# SCH_2-way_Traffic.net
KiCad netlist of a schematic drawn in Altium Designer
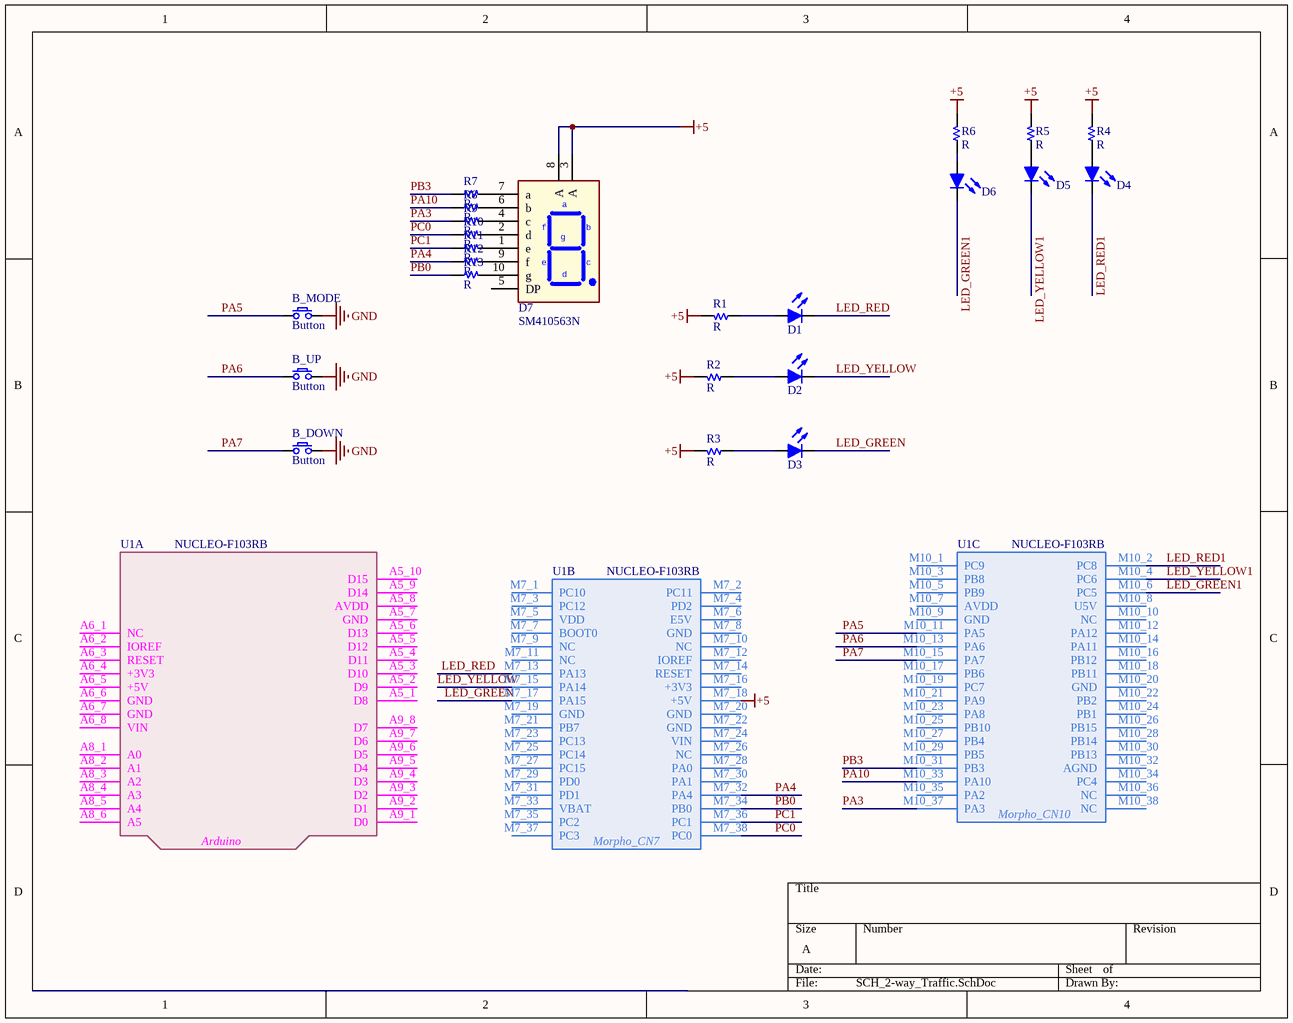
[diagram p0: SCH_2-way_Traffic.SchDoc]

(export (version "E")
  (design (tool "Eeschema 10.0.6"))
  (components
    (comp (ref "B_DOWN")
      (value "Button")
      (footprint "SW/2/DIP")
      (description "Tact switch 2 pin")
      (libsource (lib "chipfc_altium_libs") (part "SW SPST"))
    )
    (comp (ref "B_MODE")
      (value "Button")
      (footprint "SW/2/DIP")
      (description "Tact switch 2 pin")
      (libsource (lib "chipfc_altium_libs") (part "SW SPST"))
    )
    (comp (ref "B_UP")
      (value "Button")
      (footprint "SW/2/DIP")
      (description "Tact switch 2 pin")
      (libsource (lib "chipfc_altium_libs") (part "SW SPST"))
    )
    (comp (ref "D1")
      (value "Led")
      (footprint "LED 5MM - RED")
      (description "Typical LED")
      (libsource (lib "chipfc_altium_libs") (part "Led"))
    )
    (comp (ref "D2")
      (value "Led")
      (footprint "LED 5MM - WHITE")
      (description "Typical LED")
      (libsource (lib "chipfc_altium_libs") (part "Led"))
    )
    (comp (ref "D3")
      (value "Led")
      (footprint "LED 5MM - GREEN")
      (description "Typical LED")
      (libsource (lib "chipfc_altium_libs") (part "Led"))
    )
    (comp (ref "D4")
      (value "Led")
      (footprint "LED 5MM - RED")
      (description "Typical LED")
      (libsource (lib "chipfc_altium_libs") (part "Led"))
    )
    (comp (ref "D5")
      (value "Led")
      (footprint "LED 5MM - WHITE")
      (description "Typical LED")
      (libsource (lib "chipfc_altium_libs") (part "Led"))
    )
    (comp (ref "D6")
      (value "Led")
      (footprint "LED 5MM - GREEN")
      (description "Typical LED")
      (libsource (lib "chipfc_altium_libs") (part "Led"))
    )
    (comp (ref "D7")
      (value "SM410563N")
      (footprint "LED/7SEG/0.56")
      (description "SM410563N, Common-Anode, LED 7-seg, RED, 0.56\",")
      (libsource (lib "bk2022") (part "LED 7-SEG SM410563N"))
    )
    (comp (ref "R1")
      (value "R")
      (footprint "R 0805")
      (description "Resistor")
      (libsource (lib "chipfc_altium_libs") (part "Resistor"))
    )
    (comp (ref "R2")
      (value "R")
      (footprint "R 0805")
      (description "Resistor")
      (libsource (lib "chipfc_altium_libs") (part "Resistor"))
    )
    (comp (ref "R3")
      (value "R")
      (footprint "R 0805")
      (description "Resistor")
      (libsource (lib "chipfc_altium_libs") (part "Resistor"))
    )
    (comp (ref "R4")
      (value "R")
      (footprint "R 0805")
      (description "Resistor")
      (libsource (lib "chipfc_altium_libs") (part "Resistor"))
    )
    (comp (ref "R5")
      (value "R")
      (footprint "R 0805")
      (description "Resistor")
      (libsource (lib "chipfc_altium_libs") (part "Resistor"))
    )
    (comp (ref "R6")
      (value "R")
      (footprint "R 0805")
      (description "Resistor")
      (libsource (lib "chipfc_altium_libs") (part "Resistor"))
    )
    (comp (ref "R7")
      (value "R")
      (footprint "R 0805")
      (description "Resistor")
      (libsource (lib "chipfc_altium_libs") (part "Resistor"))
    )
    (comp (ref "R8")
      (value "R")
      (footprint "R 0805")
      (description "Resistor")
      (libsource (lib "chipfc_altium_libs") (part "Resistor"))
    )
    (comp (ref "R9")
      (value "R")
      (footprint "R 0805")
      (description "Resistor")
      (libsource (lib "chipfc_altium_libs") (part "Resistor"))
    )
    (comp (ref "R10")
      (value "R")
      (footprint "R 0805")
      (description "Resistor")
      (libsource (lib "chipfc_altium_libs") (part "Resistor"))
    )
    (comp (ref "R11")
      (value "R")
      (footprint "R 0805")
      (description "Resistor")
      (libsource (lib "chipfc_altium_libs") (part "Resistor"))
    )
    (comp (ref "R12")
      (value "R")
      (footprint "R 0805")
      (description "Resistor")
      (libsource (lib "chipfc_altium_libs") (part "Resistor"))
    )
    (comp (ref "R13")
      (value "R")
      (footprint "R 0805")
      (description "Resistor")
      (libsource (lib "chipfc_altium_libs") (part "Resistor"))
    )
    (comp (ref "U1")
      (value "NUCLEO-F103RB")
      (footprint "NUCLEO")
      (fields (field (name "MANUFACTURER") "STMicroelectronics"))
      (libsource (lib "nucleo") (part "NUCLEO-F103RB"))
    )
  )
  (nets
    (net (code "1") (name "+5") (class "Default")
      (node (ref "D7") (pin "3") (pinfunction "A_3") (pintype "passive"))
      (node (ref "D7") (pin "8") (pinfunction "A_8") (pintype "passive"))
      (node (ref "R1") (pin "2") (pinfunction "2_2") (pintype "passive"))
      (node (ref "R2") (pin "2") (pinfunction "2_2") (pintype "passive"))
      (node (ref "R3") (pin "2") (pinfunction "2_2") (pintype "passive"))
      (node (ref "R4") (pin "2") (pinfunction "2_2") (pintype "passive"))
      (node (ref "R5") (pin "2") (pinfunction "2_2") (pintype "passive"))
      (node (ref "R6") (pin "2") (pinfunction "2_2") (pintype "passive"))
      (node (ref "U1") (pin "M7_18") (pinfunction "+5V_M7_18") (pintype "passive"))
    )
    (net (code "2") (name "/LED_GREEN") (class "Default")
      (node (ref "D3") (pin "2") (pinfunction "K_2") (pintype "passive"))
      (node (ref "U1") (pin "M7_17") (pinfunction "PA15_M7_17") (pintype "passive"))
    )
    (net (code "3") (name "/LED_GREEN1") (class "Default")
      (node (ref "D6") (pin "2") (pinfunction "K_2") (pintype "passive"))
      (node (ref "U1") (pin "M10_6") (pinfunction "PC5_M10_6") (pintype "passive"))
    )
    (net (code "4") (name "/LED_RED") (class "Default")
      (node (ref "D1") (pin "2") (pinfunction "K_2") (pintype "passive"))
      (node (ref "U1") (pin "M7_13") (pinfunction "PA13_M7_13") (pintype "passive"))
    )
    (net (code "5") (name "/LED_RED1") (class "Default")
      (node (ref "D4") (pin "2") (pinfunction "K_2") (pintype "passive"))
      (node (ref "U1") (pin "M10_2") (pinfunction "PC8_M10_2") (pintype "passive"))
    )
    (net (code "6") (name "/LED_YELLOW") (class "Default")
      (node (ref "D2") (pin "2") (pinfunction "K_2") (pintype "passive"))
      (node (ref "U1") (pin "M7_15") (pinfunction "PA14_M7_15") (pintype "passive"))
    )
    (net (code "7") (name "/LED_YELLOW1") (class "Default")
      (node (ref "D5") (pin "2") (pinfunction "K_2") (pintype "passive"))
      (node (ref "U1") (pin "M10_4") (pinfunction "PC6_M10_4") (pintype "passive"))
    )
    (net (code "8") (name "/PA3") (class "Default")
      (node (ref "R9") (pin "1") (pinfunction "1_1") (pintype "passive"))
      (node (ref "U1") (pin "M10_37") (pinfunction "PA3_M10_37") (pintype "passive"))
    )
    (net (code "9") (name "/PA4") (class "Default")
      (node (ref "R12") (pin "1") (pinfunction "1_1") (pintype "passive"))
      (node (ref "U1") (pin "M7_32") (pinfunction "PA4_M7_32") (pintype "passive"))
    )
    (net (code "10") (name "/PA5") (class "Default")
      (node (ref "B_MODE") (pin "1") (pinfunction "1_1") (pintype "passive"))
      (node (ref "U1") (pin "M10_11") (pinfunction "PA5_M10_11") (pintype "passive"))
    )
    (net (code "11") (name "/PA6") (class "Default")
      (node (ref "B_UP") (pin "1") (pinfunction "1_1") (pintype "passive"))
      (node (ref "U1") (pin "M10_13") (pinfunction "PA6_M10_13") (pintype "passive"))
    )
    (net (code "12") (name "/PA7") (class "Default")
      (node (ref "B_DOWN") (pin "1") (pinfunction "1_1") (pintype "passive"))
      (node (ref "U1") (pin "M10_15") (pinfunction "PA7_M10_15") (pintype "passive"))
    )
    (net (code "13") (name "/PA10") (class "Default")
      (node (ref "R8") (pin "1") (pinfunction "1_1") (pintype "passive"))
      (node (ref "U1") (pin "M10_33") (pinfunction "PA10_M10_33") (pintype "passive"))
    )
    (net (code "14") (name "/PB0") (class "Default")
      (node (ref "R13") (pin "1") (pinfunction "1_1") (pintype "passive"))
      (node (ref "U1") (pin "M7_34") (pinfunction "PB0_M7_34") (pintype "passive"))
    )
    (net (code "15") (name "/PB3") (class "Default")
      (node (ref "R7") (pin "1") (pinfunction "1_1") (pintype "passive"))
      (node (ref "U1") (pin "M10_31") (pinfunction "PB3_M10_31") (pintype "passive"))
    )
    (net (code "16") (name "/PC0") (class "Default")
      (node (ref "R10") (pin "1") (pinfunction "1_1") (pintype "passive"))
      (node (ref "U1") (pin "M7_38") (pinfunction "PC0_M7_38") (pintype "passive"))
    )
    (net (code "17") (name "/PC1") (class "Default")
      (node (ref "R11") (pin "1") (pinfunction "1_1") (pintype "passive"))
      (node (ref "U1") (pin "M7_36") (pinfunction "PC1_M7_36") (pintype "passive"))
    )
    (net (code "18") (name "GND") (class "Default")
      (node (ref "B_DOWN") (pin "2") (pinfunction "2_2") (pintype "passive"))
      (node (ref "B_MODE") (pin "2") (pinfunction "2_2") (pintype "passive"))
      (node (ref "B_UP") (pin "2") (pinfunction "2_2") (pintype "passive"))
    )
    (net (code "19") (name "Net-(D1-A)") (class "Default")
      (node (ref "D1") (pin "1") (pinfunction "A_1") (pintype "passive"))
      (node (ref "R1") (pin "1") (pinfunction "1_1") (pintype "passive"))
    )
    (net (code "20") (name "Net-(D2-A)") (class "Default")
      (node (ref "D2") (pin "1") (pinfunction "A_1") (pintype "passive"))
      (node (ref "R2") (pin "1") (pinfunction "1_1") (pintype "passive"))
    )
    (net (code "21") (name "Net-(D3-A)") (class "Default")
      (node (ref "D3") (pin "1") (pinfunction "A_1") (pintype "passive"))
      (node (ref "R3") (pin "1") (pinfunction "1_1") (pintype "passive"))
    )
    (net (code "22") (name "Net-(D4-A)") (class "Default")
      (node (ref "D4") (pin "1") (pinfunction "A_1") (pintype "passive"))
      (node (ref "R4") (pin "1") (pinfunction "1_1") (pintype "passive"))
    )
    (net (code "23") (name "Net-(D5-A)") (class "Default")
      (node (ref "D5") (pin "1") (pinfunction "A_1") (pintype "passive"))
      (node (ref "R5") (pin "1") (pinfunction "1_1") (pintype "passive"))
    )
    (net (code "24") (name "Net-(D6-A)") (class "Default")
      (node (ref "D6") (pin "1") (pinfunction "A_1") (pintype "passive"))
      (node (ref "R6") (pin "1") (pinfunction "1_1") (pintype "passive"))
    )
    (net (code "25") (name "Net-(D7-a)") (class "Default")
      (node (ref "D7") (pin "7") (pinfunction "a_7") (pintype "passive"))
      (node (ref "R7") (pin "2") (pinfunction "2_2") (pintype "passive"))
    )
    (net (code "26") (name "Net-(D7-b)") (class "Default")
      (node (ref "D7") (pin "6") (pinfunction "b_6") (pintype "passive"))
      (node (ref "R8") (pin "2") (pinfunction "2_2") (pintype "passive"))
    )
    (net (code "27") (name "Net-(D7-c)") (class "Default")
      (node (ref "D7") (pin "4") (pinfunction "c_4") (pintype "passive"))
      (node (ref "R9") (pin "2") (pinfunction "2_2") (pintype "passive"))
    )
    (net (code "28") (name "Net-(D7-d)") (class "Default")
      (node (ref "D7") (pin "2") (pinfunction "d_2") (pintype "passive"))
      (node (ref "R10") (pin "2") (pinfunction "2_2") (pintype "passive"))
    )
    (net (code "29") (name "Net-(D7-e)") (class "Default")
      (node (ref "D7") (pin "1") (pinfunction "e_1") (pintype "passive"))
      (node (ref "R11") (pin "2") (pinfunction "2_2") (pintype "passive"))
    )
    (net (code "30") (name "Net-(D7-f)") (class "Default")
      (node (ref "D7") (pin "9") (pinfunction "f_9") (pintype "passive"))
      (node (ref "R12") (pin "2") (pinfunction "2_2") (pintype "passive"))
    )
    (net (code "31") (name "Net-(D7-g)") (class "Default")
      (node (ref "D7") (pin "10") (pinfunction "g_10") (pintype "passive"))
      (node (ref "R13") (pin "2") (pinfunction "2_2") (pintype "passive"))
    )
    (net (code "32") (name "unconnected-(D7-DP-Pad5)") (class "Default")
      (node (ref "D7") (pin "5") (pinfunction "DP_5") (pintype "passive"))
    )
    (net (code "33") (name "unconnected-(U1A-+3V3-PadA6_4)") (class "Default")
      (node (ref "U1") (pin "A6_4") (pinfunction "+3V3_A6_4") (pintype "passive"))
    )
    (net (code "34") (name "unconnected-(U1A-+5V-PadA6_5)") (class "Default")
      (node (ref "U1") (pin "A6_5") (pinfunction "+5V_A6_5") (pintype "passive"))
    )
    (net (code "35") (name "unconnected-(U1A-A0-PadA8_1)") (class "Default")
      (node (ref "U1") (pin "A8_1") (pinfunction "A0_A8_1") (pintype "passive"))
    )
    (net (code "36") (name "unconnected-(U1A-A1-PadA8_2)") (class "Default")
      (node (ref "U1") (pin "A8_2") (pinfunction "A1_A8_2") (pintype "passive"))
    )
    (net (code "37") (name "unconnected-(U1A-A2-PadA8_3)") (class "Default")
      (node (ref "U1") (pin "A8_3") (pinfunction "A2_A8_3") (pintype "passive"))
    )
    (net (code "38") (name "unconnected-(U1A-A3-PadA8_4)") (class "Default")
      (node (ref "U1") (pin "A8_4") (pinfunction "A3_A8_4") (pintype "passive"))
    )
    (net (code "39") (name "unconnected-(U1A-A4-PadA8_5)") (class "Default")
      (node (ref "U1") (pin "A8_5") (pinfunction "A4_A8_5") (pintype "passive"))
    )
    (net (code "40") (name "unconnected-(U1A-A5-PadA8_6)") (class "Default")
      (node (ref "U1") (pin "A8_6") (pinfunction "A5_A8_6") (pintype "passive"))
    )
    (net (code "41") (name "unconnected-(U1A-AVDD-PadA5_8)") (class "Default")
      (node (ref "U1") (pin "A5_8") (pinfunction "AVDD_A5_8") (pintype "passive"))
    )
    (net (code "42") (name "unconnected-(U1A-D0-PadA9_1)") (class "Default")
      (node (ref "U1") (pin "A9_1") (pinfunction "D0_A9_1") (pintype "passive"))
    )
    (net (code "43") (name "unconnected-(U1A-D1-PadA9_2)") (class "Default")
      (node (ref "U1") (pin "A9_2") (pinfunction "D1_A9_2") (pintype "passive"))
    )
    (net (code "44") (name "unconnected-(U1A-D2-PadA9_3)") (class "Default")
      (node (ref "U1") (pin "A9_3") (pinfunction "D2_A9_3") (pintype "passive"))
    )
    (net (code "45") (name "unconnected-(U1A-D3-PadA9_4)") (class "Default")
      (node (ref "U1") (pin "A9_4") (pinfunction "D3_A9_4") (pintype "passive"))
    )
    (net (code "46") (name "unconnected-(U1A-D4-PadA9_5)") (class "Default")
      (node (ref "U1") (pin "A9_5") (pinfunction "D4_A9_5") (pintype "passive"))
    )
    (net (code "47") (name "unconnected-(U1A-D5-PadA9_6)") (class "Default")
      (node (ref "U1") (pin "A9_6") (pinfunction "D5_A9_6") (pintype "passive"))
    )
    (net (code "48") (name "unconnected-(U1A-D6-PadA9_7)") (class "Default")
      (node (ref "U1") (pin "A9_7") (pinfunction "D6_A9_7") (pintype "passive"))
    )
    (net (code "49") (name "unconnected-(U1A-D7-PadA9_8)") (class "Default")
      (node (ref "U1") (pin "A9_8") (pinfunction "D7_A9_8") (pintype "passive"))
    )
    (net (code "50") (name "unconnected-(U1A-D8-PadA5_1)") (class "Default")
      (node (ref "U1") (pin "A5_1") (pinfunction "D8_A5_1") (pintype "passive"))
    )
    (net (code "51") (name "unconnected-(U1A-D9-PadA5_2)") (class "Default")
      (node (ref "U1") (pin "A5_2") (pinfunction "D9_A5_2") (pintype "passive"))
    )
    (net (code "52") (name "unconnected-(U1A-D10-PadA5_3)") (class "Default")
      (node (ref "U1") (pin "A5_3") (pinfunction "D10_A5_3") (pintype "passive"))
    )
    (net (code "53") (name "unconnected-(U1A-D11-PadA5_4)") (class "Default")
      (node (ref "U1") (pin "A5_4") (pinfunction "D11_A5_4") (pintype "passive"))
    )
    (net (code "54") (name "unconnected-(U1A-D12-PadA5_5)") (class "Default")
      (node (ref "U1") (pin "A5_5") (pinfunction "D12_A5_5") (pintype "passive"))
    )
    (net (code "55") (name "unconnected-(U1A-D13-PadA5_6)") (class "Default")
      (node (ref "U1") (pin "A5_6") (pinfunction "D13_A5_6") (pintype "passive"))
    )
    (net (code "56") (name "unconnected-(U1A-D14-PadA5_9)") (class "Default")
      (node (ref "U1") (pin "A5_9") (pinfunction "D14_A5_9") (pintype "passive"))
    )
    (net (code "57") (name "unconnected-(U1A-D15-PadA5_10)") (class "Default")
      (node (ref "U1") (pin "A5_10") (pinfunction "D15_A5_10") (pintype "passive"))
    )
    (net (code "58") (name "unconnected-(U1A-GND-PadA5_7)") (class "Default")
      (node (ref "U1") (pin "A5_7") (pinfunction "GND_A5_7") (pintype "passive"))
    )
    (net (code "59") (name "unconnected-(U1A-GND-PadA6_6)") (class "Default")
      (node (ref "U1") (pin "A6_6") (pinfunction "GND_A6_6") (pintype "passive"))
    )
    (net (code "60") (name "unconnected-(U1A-GND-PadA6_7)") (class "Default")
      (node (ref "U1") (pin "A6_7") (pinfunction "GND_A6_7") (pintype "passive"))
    )
    (net (code "61") (name "unconnected-(U1A-IOREF-PadA6_2)") (class "Default")
      (node (ref "U1") (pin "A6_2") (pinfunction "IOREF_A6_2") (pintype "passive"))
    )
    (net (code "62") (name "unconnected-(U1A-NC-PadA6_1)") (class "Default")
      (node (ref "U1") (pin "A6_1") (pinfunction "NC_A6_1") (pintype "passive"))
    )
    (net (code "63") (name "unconnected-(U1A-RESET-PadA6_3)") (class "Default")
      (node (ref "U1") (pin "A6_3") (pinfunction "RESET_A6_3") (pintype "passive"))
    )
    (net (code "64") (name "unconnected-(U1A-VIN-PadA6_8)") (class "Default")
      (node (ref "U1") (pin "A6_8") (pinfunction "VIN_A6_8") (pintype "passive"))
    )
    (net (code "65") (name "unconnected-(U1B-+3V3-PadM7_16)") (class "Default")
      (node (ref "U1") (pin "M7_16") (pinfunction "+3V3_M7_16") (pintype "passive"))
    )
    (net (code "66") (name "unconnected-(U1B-BOOT0-PadM7_7)") (class "Default")
      (node (ref "U1") (pin "M7_7") (pinfunction "BOOT0_M7_7") (pintype "passive"))
    )
    (net (code "67") (name "unconnected-(U1B-E5V-PadM7_6)") (class "Default")
      (node (ref "U1") (pin "M7_6") (pinfunction "E5V_M7_6") (pintype "passive"))
    )
    (net (code "68") (name "unconnected-(U1B-GND-PadM7_8)") (class "Default")
      (node (ref "U1") (pin "M7_8") (pinfunction "GND_M7_8") (pintype "passive"))
    )
    (net (code "69") (name "unconnected-(U1B-GND-PadM7_19)") (class "Default")
      (node (ref "U1") (pin "M7_19") (pinfunction "GND_M7_19") (pintype "passive"))
    )
    (net (code "70") (name "unconnected-(U1B-GND-PadM7_20)") (class "Default")
      (node (ref "U1") (pin "M7_20") (pinfunction "GND_M7_20") (pintype "passive"))
    )
    (net (code "71") (name "unconnected-(U1B-GND-PadM7_22)") (class "Default")
      (node (ref "U1") (pin "M7_22") (pinfunction "GND_M7_22") (pintype "passive"))
    )
    (net (code "72") (name "unconnected-(U1B-IOREF-PadM7_12)") (class "Default")
      (node (ref "U1") (pin "M7_12") (pinfunction "IOREF_M7_12") (pintype "passive"))
    )
    (net (code "73") (name "unconnected-(U1B-NC-PadM7_9)") (class "Default")
      (node (ref "U1") (pin "M7_9") (pinfunction "NC_M7_9") (pintype "passive"))
    )
    (net (code "74") (name "unconnected-(U1B-NC-PadM7_10)") (class "Default")
      (node (ref "U1") (pin "M7_10") (pinfunction "NC_M7_10") (pintype "passive"))
    )
    (net (code "75") (name "unconnected-(U1B-NC-PadM7_11)") (class "Default")
      (node (ref "U1") (pin "M7_11") (pinfunction "NC_M7_11") (pintype "passive"))
    )
    (net (code "76") (name "unconnected-(U1B-NC-PadM7_26)") (class "Default")
      (node (ref "U1") (pin "M7_26") (pinfunction "NC_M7_26") (pintype "passive"))
    )
    (net (code "77") (name "unconnected-(U1B-PA0-PadM7_28)") (class "Default")
      (node (ref "U1") (pin "M7_28") (pinfunction "PA0_M7_28") (pintype "passive"))
    )
    (net (code "78") (name "unconnected-(U1B-PA1-PadM7_30)") (class "Default")
      (node (ref "U1") (pin "M7_30") (pinfunction "PA1_M7_30") (pintype "passive"))
    )
    (net (code "79") (name "unconnected-(U1B-PB7-PadM7_21)") (class "Default")
      (node (ref "U1") (pin "M7_21") (pinfunction "PB7_M7_21") (pintype "passive"))
    )
    (net (code "80") (name "unconnected-(U1B-PC2-PadM7_35)") (class "Default")
      (node (ref "U1") (pin "M7_35") (pinfunction "PC2_M7_35") (pintype "passive"))
    )
    (net (code "81") (name "unconnected-(U1B-PC3-PadM7_37)") (class "Default")
      (node (ref "U1") (pin "M7_37") (pinfunction "PC3_M7_37") (pintype "passive"))
    )
    (net (code "82") (name "unconnected-(U1B-PC10-PadM7_1)") (class "Default")
      (node (ref "U1") (pin "M7_1") (pinfunction "PC10_M7_1") (pintype "passive"))
    )
    (net (code "83") (name "unconnected-(U1B-PC11-PadM7_2)") (class "Default")
      (node (ref "U1") (pin "M7_2") (pinfunction "PC11_M7_2") (pintype "passive"))
    )
    (net (code "84") (name "unconnected-(U1B-PC12-PadM7_3)") (class "Default")
      (node (ref "U1") (pin "M7_3") (pinfunction "PC12_M7_3") (pintype "passive"))
    )
    (net (code "85") (name "unconnected-(U1B-PC13-PadM7_23)") (class "Default")
      (node (ref "U1") (pin "M7_23") (pinfunction "PC13_M7_23") (pintype "passive"))
    )
    (net (code "86") (name "unconnected-(U1B-PC14-PadM7_25)") (class "Default")
      (node (ref "U1") (pin "M7_25") (pinfunction "PC14_M7_25") (pintype "passive"))
    )
    (net (code "87") (name "unconnected-(U1B-PC15-PadM7_27)") (class "Default")
      (node (ref "U1") (pin "M7_27") (pinfunction "PC15_M7_27") (pintype "passive"))
    )
    (net (code "88") (name "unconnected-(U1B-PD0-PadM7_29)") (class "Default")
      (node (ref "U1") (pin "M7_29") (pinfunction "PD0_M7_29") (pintype "passive"))
    )
    (net (code "89") (name "unconnected-(U1B-PD1-PadM7_31)") (class "Default")
      (node (ref "U1") (pin "M7_31") (pinfunction "PD1_M7_31") (pintype "passive"))
    )
    (net (code "90") (name "unconnected-(U1B-PD2-PadM7_4)") (class "Default")
      (node (ref "U1") (pin "M7_4") (pinfunction "PD2_M7_4") (pintype "passive"))
    )
    (net (code "91") (name "unconnected-(U1B-RESET-PadM7_14)") (class "Default")
      (node (ref "U1") (pin "M7_14") (pinfunction "RESET_M7_14") (pintype "passive"))
    )
    (net (code "92") (name "unconnected-(U1B-VBAT-PadM7_33)") (class "Default")
      (node (ref "U1") (pin "M7_33") (pinfunction "VBAT_M7_33") (pintype "passive"))
    )
    (net (code "93") (name "unconnected-(U1B-VDD-PadM7_5)") (class "Default")
      (node (ref "U1") (pin "M7_5") (pinfunction "VDD_M7_5") (pintype "passive"))
    )
    (net (code "94") (name "unconnected-(U1B-VIN-PadM7_24)") (class "Default")
      (node (ref "U1") (pin "M7_24") (pinfunction "VIN_M7_24") (pintype "passive"))
    )
    (net (code "95") (name "unconnected-(U1C-AGND-PadM10_32)") (class "Default")
      (node (ref "U1") (pin "M10_32") (pinfunction "AGND_M10_32") (pintype "passive"))
    )
    (net (code "96") (name "unconnected-(U1C-AVDD-PadM10_7)") (class "Default")
      (node (ref "U1") (pin "M10_7") (pinfunction "AVDD_M10_7") (pintype "passive"))
    )
    (net (code "97") (name "unconnected-(U1C-GND-PadM10_9)") (class "Default")
      (node (ref "U1") (pin "M10_9") (pinfunction "GND_M10_9") (pintype "passive"))
    )
    (net (code "98") (name "unconnected-(U1C-GND-PadM10_20)") (class "Default")
      (node (ref "U1") (pin "M10_20") (pinfunction "GND_M10_20") (pintype "passive"))
    )
    (net (code "99") (name "unconnected-(U1C-NC-PadM10_10)") (class "Default")
      (node (ref "U1") (pin "M10_10") (pinfunction "NC_M10_10") (pintype "passive"))
    )
    (net (code "100") (name "unconnected-(U1C-NC-PadM10_36)") (class "Default")
      (node (ref "U1") (pin "M10_36") (pinfunction "NC_M10_36") (pintype "passive"))
    )
    (net (code "101") (name "unconnected-(U1C-NC-PadM10_38)") (class "Default")
      (node (ref "U1") (pin "M10_38") (pinfunction "NC_M10_38") (pintype "passive"))
    )
    (net (code "102") (name "unconnected-(U1C-PA2-PadM10_35)") (class "Default")
      (node (ref "U1") (pin "M10_35") (pinfunction "PA2_M10_35") (pintype "passive"))
    )
    (net (code "103") (name "unconnected-(U1C-PA8-PadM10_23)") (class "Default")
      (node (ref "U1") (pin "M10_23") (pinfunction "PA8_M10_23") (pintype "passive"))
    )
    (net (code "104") (name "unconnected-(U1C-PA9-PadM10_21)") (class "Default")
      (node (ref "U1") (pin "M10_21") (pinfunction "PA9_M10_21") (pintype "passive"))
    )
    (net (code "105") (name "unconnected-(U1C-PA11-PadM10_14)") (class "Default")
      (node (ref "U1") (pin "M10_14") (pinfunction "PA11_M10_14") (pintype "passive"))
    )
    (net (code "106") (name "unconnected-(U1C-PA12-PadM10_12)") (class "Default")
      (node (ref "U1") (pin "M10_12") (pinfunction "PA12_M10_12") (pintype "passive"))
    )
    (net (code "107") (name "unconnected-(U1C-PB1-PadM10_24)") (class "Default")
      (node (ref "U1") (pin "M10_24") (pinfunction "PB1_M10_24") (pintype "passive"))
    )
    (net (code "108") (name "unconnected-(U1C-PB2-PadM10_22)") (class "Default")
      (node (ref "U1") (pin "M10_22") (pinfunction "PB2_M10_22") (pintype "passive"))
    )
    (net (code "109") (name "unconnected-(U1C-PB4-PadM10_27)") (class "Default")
      (node (ref "U1") (pin "M10_27") (pinfunction "PB4_M10_27") (pintype "passive"))
    )
    (net (code "110") (name "unconnected-(U1C-PB5-PadM10_29)") (class "Default")
      (node (ref "U1") (pin "M10_29") (pinfunction "PB5_M10_29") (pintype "passive"))
    )
    (net (code "111") (name "unconnected-(U1C-PB6-PadM10_17)") (class "Default")
      (node (ref "U1") (pin "M10_17") (pinfunction "PB6_M10_17") (pintype "passive"))
    )
    (net (code "112") (name "unconnected-(U1C-PB8-PadM10_3)") (class "Default")
      (node (ref "U1") (pin "M10_3") (pinfunction "PB8_M10_3") (pintype "passive"))
    )
    (net (code "113") (name "unconnected-(U1C-PB9-PadM10_5)") (class "Default")
      (node (ref "U1") (pin "M10_5") (pinfunction "PB9_M10_5") (pintype "passive"))
    )
    (net (code "114") (name "unconnected-(U1C-PB10-PadM10_25)") (class "Default")
      (node (ref "U1") (pin "M10_25") (pinfunction "PB10_M10_25") (pintype "passive"))
    )
    (net (code "115") (name "unconnected-(U1C-PB11-PadM10_18)") (class "Default")
      (node (ref "U1") (pin "M10_18") (pinfunction "PB11_M10_18") (pintype "passive"))
    )
    (net (code "116") (name "unconnected-(U1C-PB12-PadM10_16)") (class "Default")
      (node (ref "U1") (pin "M10_16") (pinfunction "PB12_M10_16") (pintype "passive"))
    )
    (net (code "117") (name "unconnected-(U1C-PB13-PadM10_30)") (class "Default")
      (node (ref "U1") (pin "M10_30") (pinfunction "PB13_M10_30") (pintype "passive"))
    )
    (net (code "118") (name "unconnected-(U1C-PB14-PadM10_28)") (class "Default")
      (node (ref "U1") (pin "M10_28") (pinfunction "PB14_M10_28") (pintype "passive"))
    )
    (net (code "119") (name "unconnected-(U1C-PB15-PadM10_26)") (class "Default")
      (node (ref "U1") (pin "M10_26") (pinfunction "PB15_M10_26") (pintype "passive"))
    )
    (net (code "120") (name "unconnected-(U1C-PC4-PadM10_34)") (class "Default")
      (node (ref "U1") (pin "M10_34") (pinfunction "PC4_M10_34") (pintype "passive"))
    )
    (net (code "121") (name "unconnected-(U1C-PC7-PadM10_19)") (class "Default")
      (node (ref "U1") (pin "M10_19") (pinfunction "PC7_M10_19") (pintype "passive"))
    )
    (net (code "122") (name "unconnected-(U1C-PC9-PadM10_1)") (class "Default")
      (node (ref "U1") (pin "M10_1") (pinfunction "PC9_M10_1") (pintype "passive"))
    )
    (net (code "123") (name "unconnected-(U1C-U5V-PadM10_8)") (class "Default")
      (node (ref "U1") (pin "M10_8") (pinfunction "U5V_M10_8") (pintype "passive"))
    )
  )
)
